# ProPrj_STM_L_2026-07-04.net
KiCad netlist of a schematic drawn in EasyEDA Pro
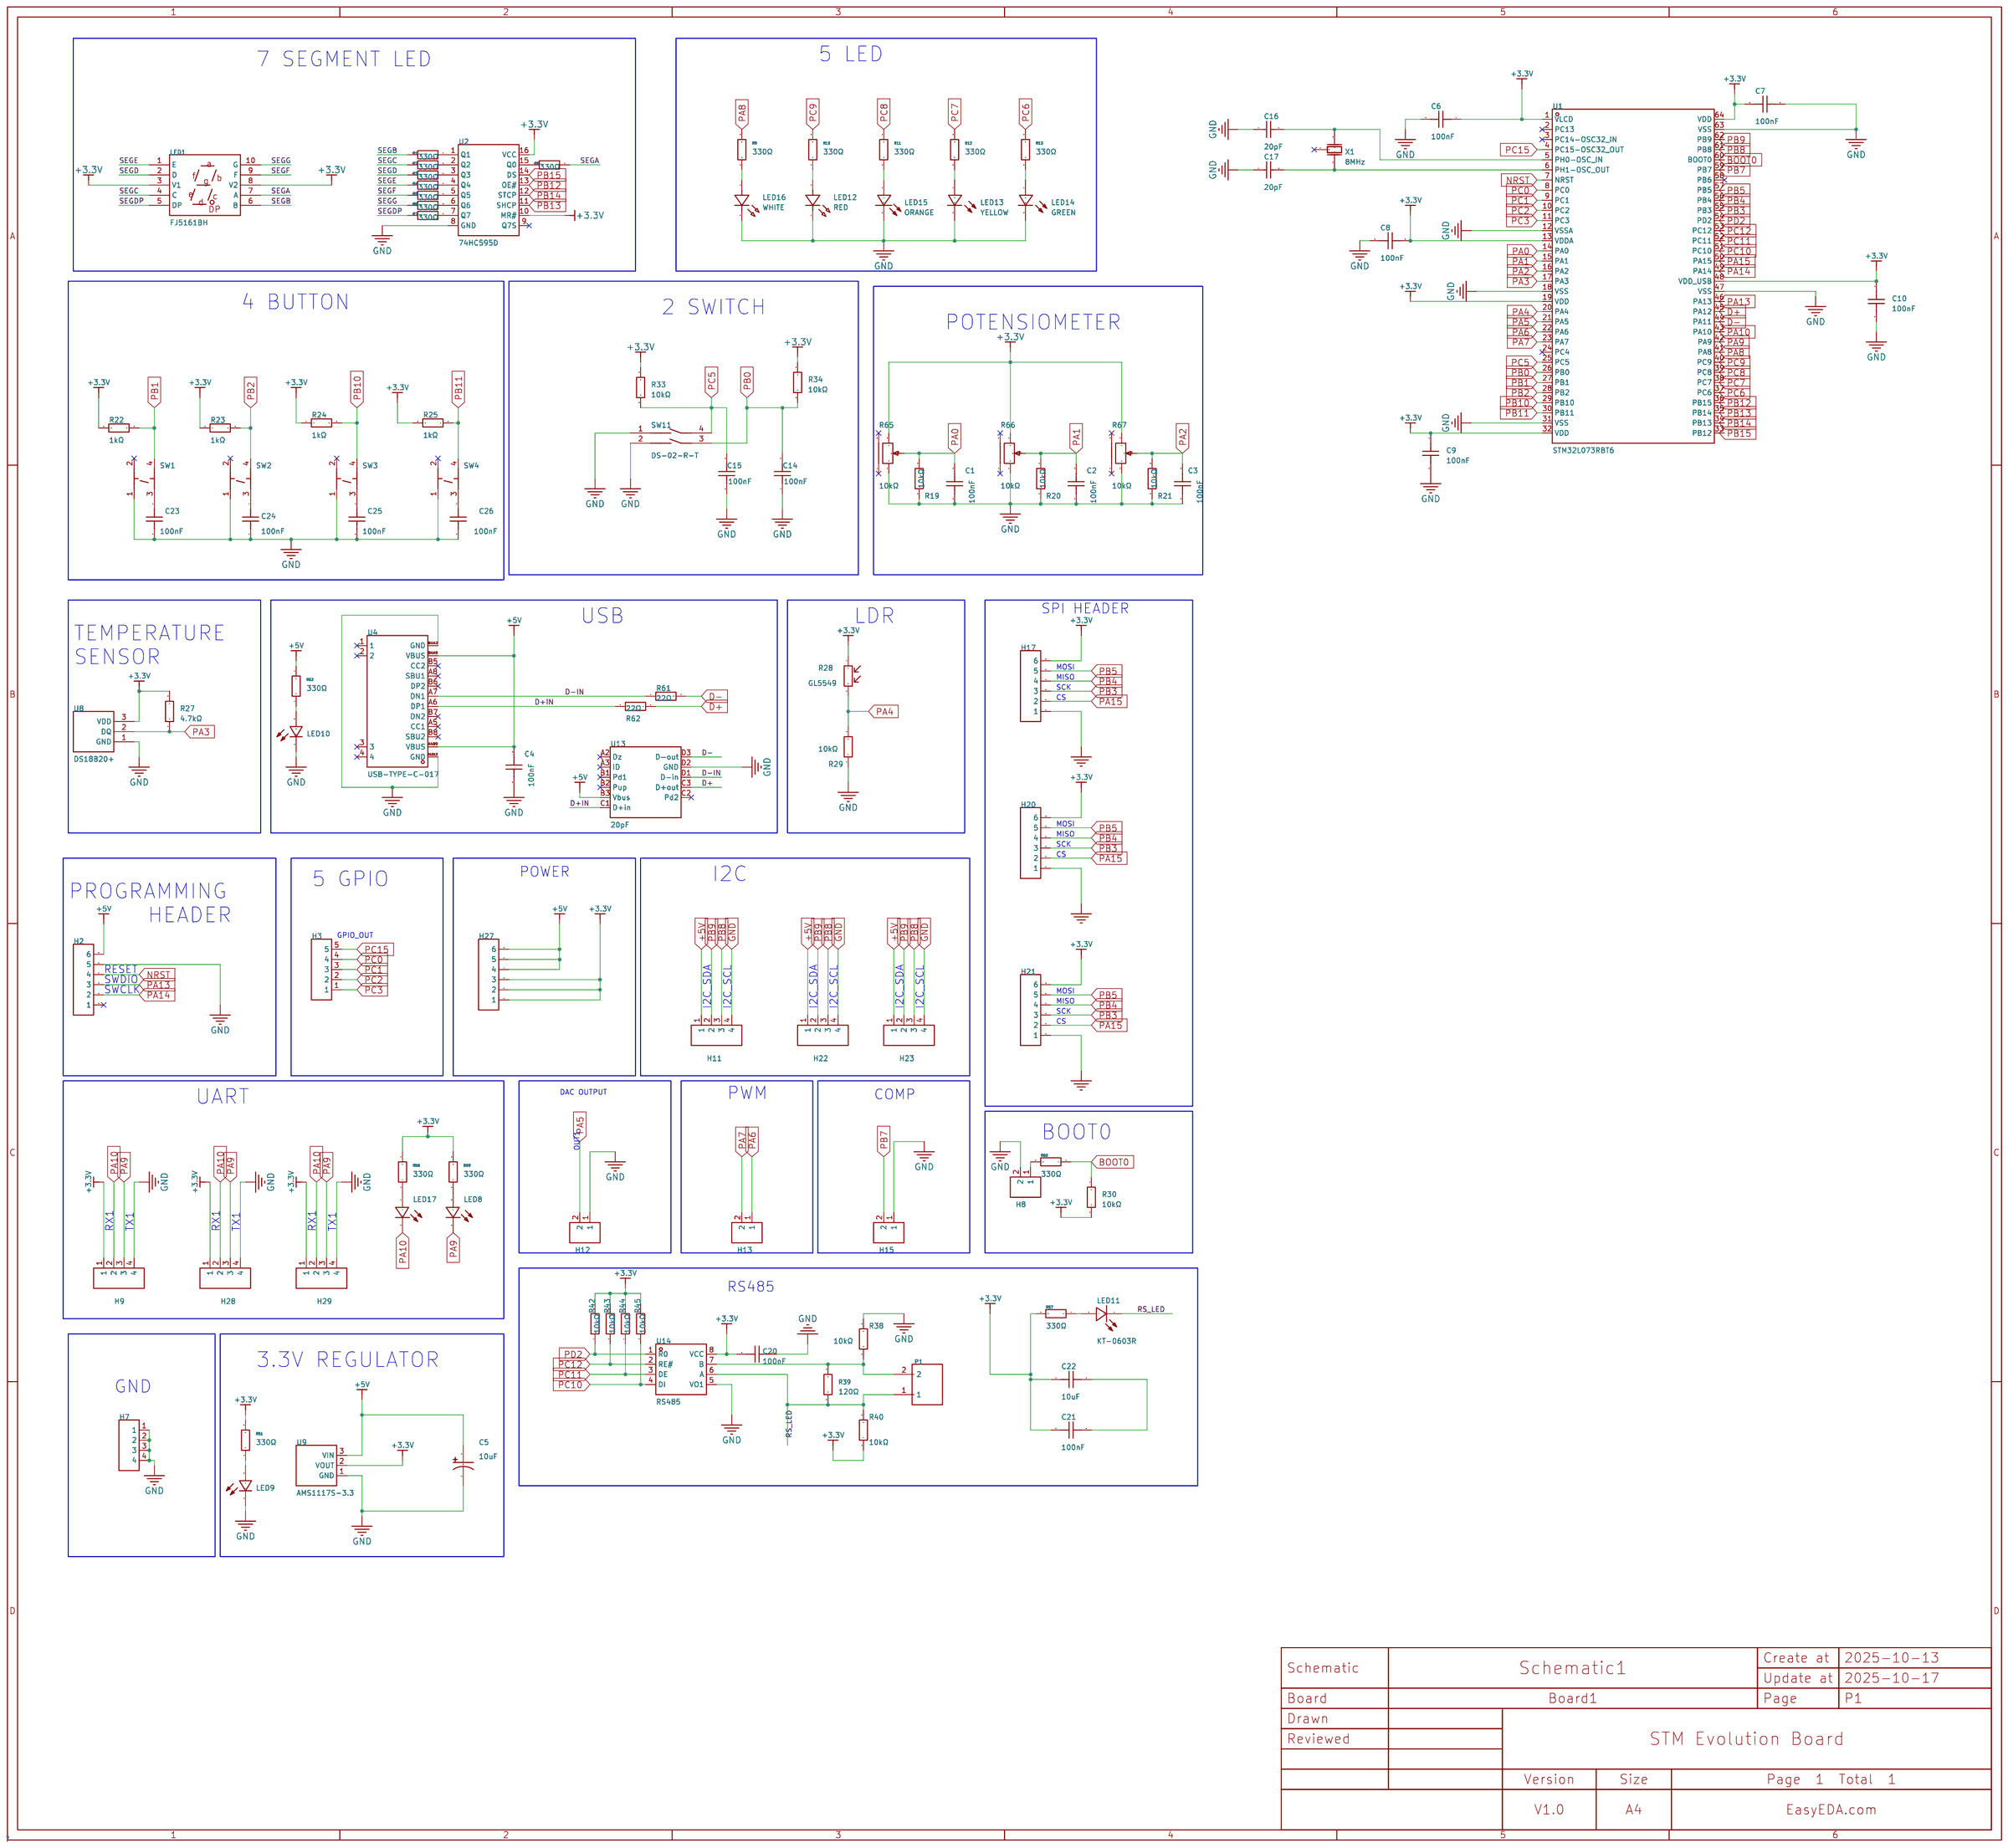
[diagram p0: schematic sheet]

(export (version "E")
  (design (tool "Eeschema 10.0.6"))
  (components
    (comp (ref "C1")
      (value "100nF")
      (footprint "easyedapro:C0603")
      (fields
        (field (name "Manufacturer Part") "CC0603KRX7R9BB104")
        (field (name "Manufacturer") "YAGEO(国巨)")
      )
      (libsource (lib "easyedapro") (part "CC0603KRX7R9BB104"))
    )
    (comp (ref "C2")
      (value "100nF")
      (footprint "easyedapro:C0603")
      (fields
        (field (name "Manufacturer Part") "CC0603KRX7R9BB104")
        (field (name "Manufacturer") "YAGEO(国巨)")
      )
      (libsource (lib "easyedapro") (part "CC0603KRX7R9BB104"))
    )
    (comp (ref "C3")
      (value "100nF")
      (footprint "easyedapro:C0603")
      (fields
        (field (name "Manufacturer Part") "CC0603KRX7R9BB104")
        (field (name "Manufacturer") "YAGEO(国巨)")
      )
      (libsource (lib "easyedapro") (part "CC0603KRX7R9BB104"))
    )
    (comp (ref "C4")
      (value "100nF")
      (footprint "easyedapro:C0603")
      (fields
        (field (name "Manufacturer Part") "CC0603KRX7R9BB104")
        (field (name "Manufacturer") "YAGEO(国巨)")
      )
      (libsource (lib "easyedapro") (part "CC0603KRX7R9BB104"))
    )
    (comp (ref "C5")
      (value "10uF")
      (footprint "easyedapro:CAP-SMD_L3.2-W1.6")
      (fields (field (name "Manufacturer Part") "NOJA106M010RWJ") (field (name "Manufacturer") "Kyocera AVX"))
      (libsource (lib "easyedapro") (part "NOJA106M010RWJ"))
    )
    (comp (ref "C6")
      (value "100nF")
      (footprint "easyedapro:C0603")
      (fields
        (field (name "Manufacturer Part") "CC0603KRX7R9BB104")
        (field (name "Manufacturer") "YAGEO(国巨)")
      )
      (libsource (lib "easyedapro") (part "CC0603KRX7R9BB104"))
    )
    (comp (ref "C7")
      (value "100nF")
      (footprint "easyedapro:C0603")
      (fields
        (field (name "Manufacturer Part") "CC0603KRX7R9BB104")
        (field (name "Manufacturer") "YAGEO(国巨)")
      )
      (libsource (lib "easyedapro") (part "CC0603KRX7R9BB104"))
    )
    (comp (ref "C8")
      (value "100nF")
      (footprint "easyedapro:C0603")
      (fields
        (field (name "Manufacturer Part") "CC0603KRX7R9BB104")
        (field (name "Manufacturer") "YAGEO(国巨)")
      )
      (libsource (lib "easyedapro") (part "CC0603KRX7R9BB104"))
    )
    (comp (ref "C9")
      (value "100nF")
      (footprint "easyedapro:C0603")
      (fields
        (field (name "Manufacturer Part") "CC0603KRX7R9BB104")
        (field (name "Manufacturer") "YAGEO(国巨)")
      )
      (libsource (lib "easyedapro") (part "CC0603KRX7R9BB104"))
    )
    (comp (ref "C10")
      (value "100nF")
      (footprint "easyedapro:C0603")
      (fields
        (field (name "Manufacturer Part") "CC0603KRX7R9BB104")
        (field (name "Manufacturer") "YAGEO(国巨)")
      )
      (libsource (lib "easyedapro") (part "CC0603KRX7R9BB104"))
    )
    (comp (ref "C14")
      (value "100nF")
      (footprint "easyedapro:C0603")
      (fields
        (field (name "Manufacturer Part") "CC0603KRX7R9BB104")
        (field (name "Manufacturer") "YAGEO(国巨)")
      )
      (libsource (lib "easyedapro") (part "CC0603KRX7R9BB104"))
    )
    (comp (ref "C15")
      (value "100nF")
      (footprint "easyedapro:C0603")
      (fields
        (field (name "Manufacturer Part") "CC0603KRX7R9BB104")
        (field (name "Manufacturer") "YAGEO(国巨)")
      )
      (libsource (lib "easyedapro") (part "CC0603KRX7R9BB104"))
    )
    (comp (ref "C16")
      (value "20pF")
      (footprint "easyedapro:C0603")
      (fields
        (field (name "Manufacturer Part") "CL10C200JB8NNNC")
        (field (name "Manufacturer") "SAMSUNG(三星)")
      )
      (libsource (lib "easyedapro") (part "CL10C200JB8NNNC"))
    )
    (comp (ref "C17")
      (value "20pF")
      (footprint "easyedapro:C0603")
      (fields
        (field (name "Manufacturer Part") "CL10C200JB8NNNC")
        (field (name "Manufacturer") "SAMSUNG(三星)")
      )
      (libsource (lib "easyedapro") (part "CL10C200JB8NNNC"))
    )
    (comp (ref "C20")
      (value "100nF")
      (footprint "easyedapro:C0603")
      (fields
        (field (name "Manufacturer Part") "CC0603KRX7R9BB104")
        (field (name "Manufacturer") "YAGEO(国巨)")
      )
      (libsource (lib "easyedapro") (part "CC0603KRX7R9BB104"))
    )
    (comp (ref "C21")
      (value "100nF")
      (footprint "easyedapro:C0603")
      (fields
        (field (name "Manufacturer Part") "CC0603KRX7R9BB104")
        (field (name "Manufacturer") "YAGEO(国巨)")
      )
      (libsource (lib "easyedapro") (part "CC0603KRX7R9BB104"))
    )
    (comp (ref "C22")
      (value "10uF")
      (footprint "easyedapro:C0603")
      (fields
        (field (name "Manufacturer Part") "CL10A106KP8NNNC")
        (field (name "Manufacturer") "SAMSUNG(三星)")
      )
      (libsource (lib "easyedapro") (part "CL10A106KP8NNNC"))
    )
    (comp (ref "C23")
      (value "100nF")
      (footprint "easyedapro:C0603")
      (description "Capacitance:100nF Tolerance:±10% Tolerance:±10% Voltage Rating:50V Temperature Coefficient:X7R")
      (fields
        (field (name "Manufacturer Part") "CC0603KRX7R9BB104")
        (field (name "Manufacturer") "YAGEO(国巨)")
      )
      (libsource (lib "easyedapro") (part "CC0603KRX7R9BB104"))
    )
    (comp (ref "C24")
      (value "100nF")
      (footprint "easyedapro:C0603")
      (description "Capacitance:100nF Tolerance:±10% Tolerance:±10% Voltage Rating:50V Temperature Coefficient:X7R")
      (fields
        (field (name "Manufacturer Part") "CC0603KRX7R9BB104")
        (field (name "Manufacturer") "YAGEO(国巨)")
      )
      (libsource (lib "easyedapro") (part "CC0603KRX7R9BB104"))
    )
    (comp (ref "C25")
      (value "100nF")
      (footprint "easyedapro:C0603")
      (description "Capacitance:100nF Tolerance:±10% Tolerance:±10% Voltage Rating:50V Temperature Coefficient:X7R")
      (fields
        (field (name "Manufacturer Part") "CC0603KRX7R9BB104")
        (field (name "Manufacturer") "YAGEO(国巨)")
      )
      (libsource (lib "easyedapro") (part "CC0603KRX7R9BB104"))
    )
    (comp (ref "C26")
      (value "100nF")
      (footprint "easyedapro:C0603")
      (description "Capacitance:100nF Tolerance:±10% Tolerance:±10% Voltage Rating:50V Temperature Coefficient:X7R")
      (fields
        (field (name "Manufacturer Part") "CC0603KRX7R9BB104")
        (field (name "Manufacturer") "YAGEO(国巨)")
      )
      (libsource (lib "easyedapro") (part "CC0603KRX7R9BB104"))
    )
    (comp (ref "H2")
      (value "2.54-1x6P直针")
      (footprint "easyedapro:HDR-TH_6P-P2.54-V-M-1")
      (fields (field (name "Manufacturer") "BOOMELE(博穆精密)"))
      (libsource (lib "easyedapro") (part "Header-Male-2.54_1x6"))
    )
    (comp (ref "H3")
      (value "PH2.54-1X5P-H25")
      (footprint "easyedapro:HDR-TH_5P-P2.54-V-M-3")
      (fields (field (name "Manufacturer") "JXTCONN(聚兴泰)"))
      (libsource (lib "easyedapro") (part "PH2.54-1X5P-H25"))
    )
    (comp (ref "H7")
      (value "PZ2.54-1X4P-H25")
      (footprint "easyedapro:HDR-TH_4P-P2.54-V-M")
      (fields (field (name "Manufacturer") "JXTCONN(聚兴泰)"))
      (libsource (lib "easyedapro") (part "PZ2.54-1X4P-H25"))
    )
    (comp (ref "H8")
      (value "1.27-1*2P针")
      (footprint "easyedapro:HDR-TH_2P-P1.27-V-M")
      (fields (field (name "Manufacturer") "BOOMELE(博穆精密)"))
      (libsource (lib "easyedapro") (part "1.27MM/1*2P"))
    )
    (comp (ref "H9")
      (value "PZ2.54-1X4P-H25")
      (footprint "easyedapro:HDR-TH_4P-P2.54-V-M")
      (fields (field (name "Manufacturer") "JXTCONN(聚兴泰)"))
      (libsource (lib "easyedapro") (part "PZ2.54-1X4P-H25"))
    )
    (comp (ref "H11")
      (value "PZ2.54-1X4P-H25")
      (footprint "easyedapro:HDR-TH_4P-P2.54-V-M")
      (fields (field (name "Manufacturer") "JXTCONN(聚兴泰)"))
      (libsource (lib "easyedapro") (part "PZ2.54-1X4P-H25"))
    )
    (comp (ref "H12")
      (value "1.27-1*2P针")
      (footprint "easyedapro:HDR-TH_2P-P1.27-V-M")
      (fields (field (name "Manufacturer") "BOOMELE(博穆精密)"))
      (libsource (lib "easyedapro") (part "1.27MM/1*2P"))
    )
    (comp (ref "H13")
      (value "1.27-1*2P针")
      (footprint "easyedapro:HDR-TH_2P-P1.27-V-M")
      (fields (field (name "Manufacturer") "BOOMELE(博穆精密)"))
      (libsource (lib "easyedapro") (part "1.27MM/1*2P"))
    )
    (comp (ref "H15")
      (value "1.27-1*2P针")
      (footprint "easyedapro:HDR-TH_2P-P1.27-V-M")
      (fields (field (name "Manufacturer") "BOOMELE(博穆精密)"))
      (libsource (lib "easyedapro") (part "1.27MM/1*2P"))
    )
    (comp (ref "H17")
      (value "2.54-1x6P直针")
      (footprint "easyedapro:HDR-TH_6P-P2.54-V-M-1")
      (fields (field (name "Manufacturer") "BOOMELE(博穆精密)"))
      (libsource (lib "easyedapro") (part "Header-Male-2.54_1x6"))
    )
    (comp (ref "H20")
      (value "2.54-1x6P直针")
      (footprint "easyedapro:HDR-TH_6P-P2.54-V-M-1")
      (fields (field (name "Manufacturer") "BOOMELE(博穆精密)"))
      (libsource (lib "easyedapro") (part "Header-Male-2.54_1x6"))
    )
    (comp (ref "H21")
      (value "2.54-1x6P直针")
      (footprint "easyedapro:HDR-TH_6P-P2.54-V-M-1")
      (fields (field (name "Manufacturer") "BOOMELE(博穆精密)"))
      (libsource (lib "easyedapro") (part "Header-Male-2.54_1x6"))
    )
    (comp (ref "H22")
      (value "PZ2.54-1X4P-H25")
      (footprint "easyedapro:HDR-TH_4P-P2.54-V-M")
      (fields (field (name "Manufacturer") "JXTCONN(聚兴泰)"))
      (libsource (lib "easyedapro") (part "PZ2.54-1X4P-H25"))
    )
    (comp (ref "H23")
      (value "PZ2.54-1X4P-H25")
      (footprint "easyedapro:HDR-TH_4P-P2.54-V-M")
      (fields (field (name "Manufacturer") "JXTCONN(聚兴泰)"))
      (libsource (lib "easyedapro") (part "PZ2.54-1X4P-H25"))
    )
    (comp (ref "H27")
      (value "2.54-1x6P直针")
      (footprint "easyedapro:HDR-TH_6P-P2.54-V-M-1")
      (fields (field (name "Manufacturer") "BOOMELE(博穆精密)"))
      (libsource (lib "easyedapro") (part "Header-Male-2.54_1x6"))
    )
    (comp (ref "H28")
      (value "PZ2.54-1X4P-H25")
      (footprint "easyedapro:HDR-TH_4P-P2.54-V-M")
      (fields (field (name "Manufacturer") "JXTCONN(聚兴泰)"))
      (libsource (lib "easyedapro") (part "PZ2.54-1X4P-H25"))
    )
    (comp (ref "H29")
      (value "PZ2.54-1X4P-H25")
      (footprint "easyedapro:HDR-TH_4P-P2.54-V-M")
      (fields (field (name "Manufacturer") "JXTCONN(聚兴泰)"))
      (libsource (lib "easyedapro") (part "PZ2.54-1X4P-H25"))
    )
    (comp (ref "LED1")
      (value "FJ5161BH")
      (footprint "easyedapro:LED-SEG-TH_FJ5161BH")
      (fields (field (name "Manufacturer") "志浩"))
      (libsource (lib "easyedapro") (part "FJ5161BH"))
    )
    (comp (ref "LED8")
      (value "YLED0603R")
      (footprint "easyedapro:LED0603-FD")
      (fields (field (name "Manufacturer") "YONGYUTAI(永裕泰)"))
      (libsource (lib "easyedapro") (part "YLED0603R"))
    )
    (comp (ref "LED9")
      (value "NCD0603G1")
      (footprint "easyedapro:LED0603-RD_1")
      (fields (field (name "Manufacturer") "国星光电"))
      (libsource (lib "easyedapro") (part "FC-D1608UGK-520D10"))
    )
    (comp (ref "LED10")
      (value "NCD0603G1")
      (footprint "easyedapro:LED0603-RD_1")
      (fields (field (name "Manufacturer") "国星光电"))
      (libsource (lib "easyedapro") (part "FC-D1608UGK-520D10"))
    )
    (comp (ref "LED11")
      (value "KT-0603R")
      (footprint "easyedapro:LED0603-RD")
      (fields (field (name "Manufacturer") "KENTO"))
      (libsource (lib "easyedapro") (part "KT-0603R"))
    )
    (comp (ref "LED12")
      (value "RED")
      (footprint "easyedapro:LED-TH_BD3.8-P2.54-RD")
      (fields (field (name "Manufacturer") "XINGLIGHT(成兴光)"))
      (libsource (lib "easyedapro") (part "XL-302SURD"))
    )
    (comp (ref "LED13")
      (value "YELLOW")
      (footprint "easyedapro:LED-TH_BD4.0-P2.54-FD")
      (fields (field (name "Manufacturer") "EVERLIGHT(亿光)"))
      (libsource (lib "easyedapro") (part "204-10UYT/S530-A3"))
    )
    (comp (ref "LED14")
      (value "GREEN")
      (footprint "easyedapro:LED-TH_BD4.0-P2.54-FD")
      (fields (field (name "Manufacturer") "EVERLIGHT(亿光)"))
      (libsource (lib "easyedapro") (part "204-10UYT/S530-A3"))
    )
    (comp (ref "LED15")
      (value "ORANGE")
      (footprint "easyedapro:LED-TH_BD3.0-P2.54-FD")
      (fields (field (name "Manufacturer") "TOGIALED(统佳)"))
      (libsource (lib "easyedapro") (part "TJ-L3FYTXHAMCGLFLC0A-A5"))
    )
    (comp (ref "LED16")
      (value "WHITE")
      (footprint "easyedapro:LED-TH_BD3.8-P2.54-FD_WHITE")
      (fields (field (name "Manufacturer") "XINGLIGHT(成兴光)"))
      (libsource (lib "easyedapro") (part "XL-302UWC"))
    )
    (comp (ref "LED17")
      (value "YLED0603R")
      (footprint "easyedapro:LED0603-FD")
      (fields (field (name "Manufacturer") "YONGYUTAI(永裕泰)"))
      (libsource (lib "easyedapro") (part "YLED0603R"))
    )
    (comp (ref "P1")
      (value "WJ126V-5.0-2P")
      (footprint "easyedapro:CONN-TH_WJ126V-5.0-2P")
      (fields (field (name "Manufacturer") "KANGNEX(康奈克斯电气)"))
      (libsource (lib "easyedapro") (part "WJ126V-5.0-2P"))
    )
    (comp (ref "R1")
      (value "330Ω")
      (footprint "easyedapro:R0603")
      (fields (field (name "Manufacturer Part") "RC0603FR-07330RL") (field (name "Manufacturer") "YAGEO(国巨)"))
      (libsource (lib "easyedapro") (part "RC0603FR-07330RL"))
    )
    (comp (ref "R2")
      (value "330Ω")
      (footprint "easyedapro:R0603")
      (fields (field (name "Manufacturer Part") "RC0603FR-07330RL") (field (name "Manufacturer") "YAGEO(国巨)"))
      (libsource (lib "easyedapro") (part "RC0603FR-07330RL"))
    )
    (comp (ref "R3")
      (value "330Ω")
      (footprint "easyedapro:R0603")
      (fields (field (name "Manufacturer Part") "RC0603FR-07330RL") (field (name "Manufacturer") "YAGEO(国巨)"))
      (libsource (lib "easyedapro") (part "RC0603FR-07330RL"))
    )
    (comp (ref "R4")
      (value "330Ω")
      (footprint "easyedapro:R0603")
      (fields (field (name "Manufacturer Part") "RC0603FR-07330RL") (field (name "Manufacturer") "YAGEO(国巨)"))
      (libsource (lib "easyedapro") (part "RC0603FR-07330RL"))
    )
    (comp (ref "R5")
      (value "330Ω")
      (footprint "easyedapro:R0603")
      (fields (field (name "Manufacturer Part") "RC0603FR-07330RL") (field (name "Manufacturer") "YAGEO(国巨)"))
      (libsource (lib "easyedapro") (part "RC0603FR-07330RL"))
    )
    (comp (ref "R6")
      (value "330Ω")
      (footprint "easyedapro:R0603")
      (fields (field (name "Manufacturer Part") "RC0603FR-07330RL") (field (name "Manufacturer") "YAGEO(国巨)"))
      (libsource (lib "easyedapro") (part "RC0603FR-07330RL"))
    )
    (comp (ref "R7")
      (value "330Ω")
      (footprint "easyedapro:R0603")
      (fields (field (name "Manufacturer Part") "RC0603FR-07330RL") (field (name "Manufacturer") "YAGEO(国巨)"))
      (libsource (lib "easyedapro") (part "RC0603FR-07330RL"))
    )
    (comp (ref "R8")
      (value "330Ω")
      (footprint "easyedapro:R0603")
      (fields (field (name "Manufacturer Part") "RC0603FR-07330RL") (field (name "Manufacturer") "YAGEO(国巨)"))
      (libsource (lib "easyedapro") (part "RC0603FR-07330RL"))
    )
    (comp (ref "R9")
      (value "330Ω")
      (footprint "easyedapro:R0603")
      (fields (field (name "Manufacturer Part") "RC0603FR-07330RL") (field (name "Manufacturer") "YAGEO(国巨)"))
      (libsource (lib "easyedapro") (part "RC0603FR-07330RL"))
    )
    (comp (ref "R10")
      (value "330Ω")
      (footprint "easyedapro:R0603")
      (fields (field (name "Manufacturer Part") "RC0603FR-07330RL") (field (name "Manufacturer") "YAGEO(国巨)"))
      (libsource (lib "easyedapro") (part "RC0603FR-07330RL"))
    )
    (comp (ref "R11")
      (value "330Ω")
      (footprint "easyedapro:R0603")
      (fields (field (name "Manufacturer Part") "RC0603FR-07330RL") (field (name "Manufacturer") "YAGEO(国巨)"))
      (libsource (lib "easyedapro") (part "RC0603FR-07330RL"))
    )
    (comp (ref "R12")
      (value "330Ω")
      (footprint "easyedapro:R0603")
      (fields (field (name "Manufacturer Part") "RC0603FR-07330RL") (field (name "Manufacturer") "YAGEO(国巨)"))
      (libsource (lib "easyedapro") (part "RC0603FR-07330RL"))
    )
    (comp (ref "R13")
      (value "330Ω")
      (footprint "easyedapro:R0603")
      (fields (field (name "Manufacturer Part") "RC0603FR-07330RL") (field (name "Manufacturer") "YAGEO(国巨)"))
      (libsource (lib "easyedapro") (part "RC0603FR-07330RL"))
    )
    (comp (ref "R19")
      (value "10kΩ")
      (footprint "easyedapro:R0603")
      (fields (field (name "Manufacturer Part") "RC0603FR-0710KL") (field (name "Manufacturer") "YAGEO(国巨)"))
      (libsource (lib "easyedapro") (part "RC0603FR-0710KL"))
    )
    (comp (ref "R20")
      (value "10kΩ")
      (footprint "easyedapro:R0603")
      (fields (field (name "Manufacturer Part") "RC0603FR-0710KL") (field (name "Manufacturer") "YAGEO(国巨)"))
      (libsource (lib "easyedapro") (part "RC0603FR-0710KL"))
    )
    (comp (ref "R21")
      (value "10kΩ")
      (footprint "easyedapro:R0603")
      (fields (field (name "Manufacturer Part") "RC0603FR-0710KL") (field (name "Manufacturer") "YAGEO(国巨)"))
      (libsource (lib "easyedapro") (part "RC0603FR-0710KL"))
    )
    (comp (ref "R22")
      (value "1kΩ")
      (footprint "easyedapro:R0603")
      (fields
        (field (name "Manufacturer Part") "RC0603FR-071KL")
        (field (name "Manufacturer") "YAGEO(国巨)")
        (field (name "Tolerance") "±1%")
      )
      (libsource (lib "easyedapro") (part "RC0603FR-071KL"))
    )
    (comp (ref "R23")
      (value "1kΩ")
      (footprint "easyedapro:R0603")
      (fields
        (field (name "Manufacturer Part") "RC0603FR-071KL")
        (field (name "Manufacturer") "YAGEO(国巨)")
        (field (name "Tolerance") "±1%")
      )
      (libsource (lib "easyedapro") (part "RC0603FR-071KL"))
    )
    (comp (ref "R24")
      (value "1kΩ")
      (footprint "easyedapro:R0603")
      (fields
        (field (name "Manufacturer Part") "RC0603FR-071KL")
        (field (name "Manufacturer") "YAGEO(国巨)")
        (field (name "Tolerance") "±1%")
      )
      (libsource (lib "easyedapro") (part "RC0603FR-071KL"))
    )
    (comp (ref "R25")
      (value "1kΩ")
      (footprint "easyedapro:R0603")
      (fields
        (field (name "Manufacturer Part") "RC0603FR-071KL")
        (field (name "Manufacturer") "YAGEO(国巨)")
        (field (name "Tolerance") "±1%")
      )
      (libsource (lib "easyedapro") (part "RC0603FR-071KL"))
    )
    (comp (ref "R27")
      (value "4.7kΩ")
      (footprint "easyedapro:R0603")
      (fields (field (name "Manufacturer Part") "RC0603FR-074K7L") (field (name "Manufacturer") "YAGEO(国巨)"))
      (libsource (lib "easyedapro") (part "RC0603FR-074K7L"))
    )
    (comp (ref "R28")
      (value "GL5549")
      (footprint "easyedapro:RES-TH_L5.1-W4.3-P3.40-D0.5")
      (fields (field (name "Manufacturer") "森霸"))
      (libsource (lib "easyedapro") (part "GL5549"))
    )
    (comp (ref "R29")
      (value "10kΩ")
      (footprint "easyedapro:R0603")
      (fields (field (name "Manufacturer Part") "RC0603FR-0710KL") (field (name "Manufacturer") "YAGEO(国巨)"))
      (libsource (lib "easyedapro") (part "RC0603FR-0710KL"))
    )
    (comp (ref "R30")
      (value "10kΩ")
      (footprint "easyedapro:R0603")
      (fields (field (name "Manufacturer Part") "RC0603FR-0710KL") (field (name "Manufacturer") "YAGEO(国巨)"))
      (libsource (lib "easyedapro") (part "RC0603FR-0710KL"))
    )
    (comp (ref "R33")
      (value "10kΩ")
      (footprint "easyedapro:R0603")
      (fields (field (name "Manufacturer Part") "RC0603FR-0710KL") (field (name "Manufacturer") "YAGEO(国巨)"))
      (libsource (lib "easyedapro") (part "RC0603FR-0710KL"))
    )
    (comp (ref "R34")
      (value "10kΩ")
      (footprint "easyedapro:R0603")
      (fields (field (name "Manufacturer Part") "RC0603FR-0710KL") (field (name "Manufacturer") "YAGEO(国巨)"))
      (libsource (lib "easyedapro") (part "RC0603FR-0710KL"))
    )
    (comp (ref "R38")
      (value "10kΩ")
      (footprint "easyedapro:R0603")
      (fields (field (name "Manufacturer Part") "RC0603FR-0710KL") (field (name "Manufacturer") "YAGEO(国巨)"))
      (libsource (lib "easyedapro") (part "RC0603FR-0710KL"))
    )
    (comp (ref "R39")
      (value "120Ω")
      (footprint "easyedapro:R0603")
      (fields
        (field (name "Manufacturer Part") "0603WAF1200T5E")
        (field (name "Manufacturer") "UNI-ROYAL(厚声)")
      )
      (libsource (lib "easyedapro") (part "0603WAF1200T5E"))
    )
    (comp (ref "R40")
      (value "10kΩ")
      (footprint "easyedapro:R0603")
      (fields (field (name "Manufacturer Part") "RC0603FR-0710KL") (field (name "Manufacturer") "YAGEO(国巨)"))
      (libsource (lib "easyedapro") (part "RC0603FR-0710KL"))
    )
    (comp (ref "R42")
      (value "10kΩ")
      (footprint "easyedapro:R0603")
      (fields (field (name "Manufacturer Part") "RC0603FR-0710KL") (field (name "Manufacturer") "YAGEO(国巨)"))
      (libsource (lib "easyedapro") (part "RC0603FR-0710KL"))
    )
    (comp (ref "R43")
      (value "10kΩ")
      (footprint "easyedapro:R0603")
      (fields (field (name "Manufacturer Part") "RC0603FR-0710KL") (field (name "Manufacturer") "YAGEO(国巨)"))
      (libsource (lib "easyedapro") (part "RC0603FR-0710KL"))
    )
    (comp (ref "R44")
      (value "10kΩ")
      (footprint "easyedapro:R0603")
      (fields (field (name "Manufacturer Part") "RC0603FR-0710KL") (field (name "Manufacturer") "YAGEO(国巨)"))
      (libsource (lib "easyedapro") (part "RC0603FR-0710KL"))
    )
    (comp (ref "R45")
      (value "10kΩ")
      (footprint "easyedapro:R0603")
      (fields (field (name "Manufacturer Part") "RC0603FR-0710KL") (field (name "Manufacturer") "YAGEO(国巨)"))
      (libsource (lib "easyedapro") (part "RC0603FR-0710KL"))
    )
    (comp (ref "R51")
      (value "330Ω")
      (footprint "easyedapro:R0603")
      (fields (field (name "Manufacturer Part") "RC0603FR-07330RL") (field (name "Manufacturer") "YAGEO(国巨)"))
      (libsource (lib "easyedapro") (part "RC0603FR-07330RL"))
    )
    (comp (ref "R52")
      (value "330Ω")
      (footprint "easyedapro:R0603")
      (fields (field (name "Manufacturer Part") "RC0603FR-07330RL") (field (name "Manufacturer") "YAGEO(国巨)"))
      (libsource (lib "easyedapro") (part "RC0603FR-07330RL"))
    )
    (comp (ref "R57")
      (value "330Ω")
      (footprint "easyedapro:R0603")
      (fields (field (name "Manufacturer Part") "RC0603FR-07330RL") (field (name "Manufacturer") "YAGEO(国巨)"))
      (libsource (lib "easyedapro") (part "RC0603FR-07330RL"))
    )
    (comp (ref "R58")
      (value "330Ω")
      (footprint "easyedapro:R0603")
      (fields (field (name "Manufacturer Part") "RC0603FR-07330RL") (field (name "Manufacturer") "YAGEO(国巨)"))
      (libsource (lib "easyedapro") (part "RC0603FR-07330RL"))
    )
    (comp (ref "R59")
      (value "330Ω")
      (footprint "easyedapro:R0603")
      (fields (field (name "Manufacturer Part") "RC0603FR-07330RL") (field (name "Manufacturer") "YAGEO(国巨)"))
      (libsource (lib "easyedapro") (part "RC0603FR-07330RL"))
    )
    (comp (ref "R60")
      (value "330Ω")
      (footprint "easyedapro:R0603")
      (fields (field (name "Manufacturer Part") "RC0603FR-07330RL") (field (name "Manufacturer") "YAGEO(国巨)"))
      (libsource (lib "easyedapro") (part "RC0603FR-07330RL"))
    )
    (comp (ref "R61")
      (value "22Ω")
      (footprint "easyedapro:R0603")
      (fields
        (field (name "Manufacturer Part") "0603WAF220JT5E")
        (field (name "Manufacturer") "UNI-ROYAL(厚声)")
      )
      (libsource (lib "easyedapro") (part "0603WAF220JT5E"))
    )
    (comp (ref "R62")
      (value "22Ω")
      (footprint "easyedapro:R0603")
      (fields
        (field (name "Manufacturer Part") "0603WAF220JT5E")
        (field (name "Manufacturer") "UNI-ROYAL(厚声)")
      )
      (libsource (lib "easyedapro") (part "0603WAF220JT5E"))
    )
    (comp (ref "R65")
      (value "10kΩ")
      (footprint "easyedapro:RES-ADJ-TH_RK09K1130AJ3")
      (fields
        (field (name "Manufacturer Part") "RK09K1130AP5")
        (field (name "Manufacturer") "ALPSALPINE(阿尔卑斯阿尔派)")
      )
      (libsource (lib "easyedapro") (part "RK09K1130AP5"))
    )
    (comp (ref "R66")
      (value "10kΩ")
      (footprint "easyedapro:RES-ADJ-TH_RK09K1130AJ3")
      (fields
        (field (name "Manufacturer Part") "RK09K1130AP5")
        (field (name "Manufacturer") "ALPSALPINE(阿尔卑斯阿尔派)")
      )
      (libsource (lib "easyedapro") (part "RK09K1130AP5"))
    )
    (comp (ref "R67")
      (value "10kΩ")
      (footprint "easyedapro:RES-ADJ-TH_RK09K1130AJ3")
      (fields
        (field (name "Manufacturer Part") "RK09K1130AP5")
        (field (name "Manufacturer") "ALPSALPINE(阿尔卑斯阿尔派)")
      )
      (libsource (lib "easyedapro") (part "RK09K1130AP5"))
    )
    (comp (ref "SW1")
      (value "LXW-TS-6X6X5-SMD")
      (footprint "easyedapro:SW-SMD_4P-L6.0-W6.0-P4.50-LS7.2")
      (fields (field (name "Manufacturer") "LXWCONN(连兴旺电子)"))
      (libsource (lib "easyedapro") (part "LXW-TS-6X6X5-SMD"))
    )
    (comp (ref "SW2")
      (value "LXW-TS-6X6X5-SMD")
      (footprint "easyedapro:SW-SMD_4P-L6.0-W6.0-P4.50-LS7.2")
      (fields (field (name "Manufacturer") "LXWCONN(连兴旺电子)"))
      (libsource (lib "easyedapro") (part "LXW-TS-6X6X5-SMD"))
    )
    (comp (ref "SW3")
      (value "LXW-TS-6X6X5-SMD")
      (footprint "easyedapro:SW-SMD_4P-L6.0-W6.0-P4.50-LS7.2")
      (fields (field (name "Manufacturer") "LXWCONN(连兴旺电子)"))
      (libsource (lib "easyedapro") (part "LXW-TS-6X6X5-SMD"))
    )
    (comp (ref "SW4")
      (value "LXW-TS-6X6X5-SMD")
      (footprint "easyedapro:SW-SMD_4P-L6.0-W6.0-P4.50-LS7.2")
      (fields (field (name "Manufacturer") "LXWCONN(连兴旺电子)"))
      (libsource (lib "easyedapro") (part "LXW-TS-6X6X5-SMD"))
    )
    (comp (ref "SW11")
      (value "DS-02-R-T")
      (footprint "easyedapro:SW-TH_4P-P2.54_DS-02R")
      (fields (field (name "Manufacturer") "康深"))
      (libsource (lib "easyedapro") (part "DS-02-R-T"))
    )
    (comp (ref "U1")
      (value "STM32L073RBT6")
      (footprint "easyedapro:LQFP-64_L10.0-W10.0-P0.50-LS12.0-BL")
      (fields (field (name "Manufacturer") "ST(意法半导体)"))
      (libsource (lib "easyedapro") (part "STM32L073RBT6_C2917159"))
    )
    (comp (ref "U2")
      (value "74HC595D")
      (footprint "easyedapro:SOIC-16_L9.9-W3.9-P1.27-LS6.0-BL")
      (fields (field (name "Manufacturer") "Nexperia(安世)"))
      (libsource (lib "easyedapro") (part "74HC595D,118"))
    )
    (comp (ref "U4")
      (value "USB-TYPE-C-017")
      (footprint "easyedapro:USB-TYPE-C-SMD_C9900008089")
      (fields (field (name "Manufacturer") "DEALON(德艺隆)"))
      (libsource (lib "easyedapro") (part "USB-TYPE-C-017"))
    )
    (comp (ref "U8")
      (value "DS18B20+")
      (footprint "easyedapro:TO-92-3_L4.9-W3.7-P1.27-L")
      (fields (field (name "Manufacturer") "ADI(亚德诺)/MAXIM(美信)"))
      (libsource (lib "easyedapro") (part "DS18B20+"))
    )
    (comp (ref "U9")
      (value "AMS1117S-3.3")
      (footprint "easyedapro:SOT-89-3_L4.5-W2.5-P1.50-LS4.1-BR")
      (fields (field (name "Manufacturer") "JSMSEMI(杰盛微)"))
      (libsource (lib "easyedapro") (part "AMS1117S-3.3"))
    )
    (comp (ref "U13")
      (value "20pF")
      (footprint "easyedapro:BGA-11_L2.0-W1.4-P0.50-TL")
      (fields (field (name "Manufacturer Part") "EMIF02-USB03F2") (field (name "Manufacturer") "ST(意法半导体)"))
      (libsource (lib "easyedapro") (part "EMIF02-USB03F2"))
    )
    (comp (ref "U14")
      (value "RS485")
      (footprint "easyedapro:SOP-8_L4.9-W3.9-P1.27-LS6.0-BL")
      (fields (field (name "Manufacturer") "GR(国睿)"))
      (libsource (lib "easyedapro") (part "RS485"))
    )
    (comp (ref "X1")
      (value "8MHz")
      (footprint "easyedapro:OSC-SMD_3P-L3.2-W1.3-P1.20-L")
      (fields
        (field (name "Manufacturer Part") "CSTNE8M00GH5C000R0")
        (field (name "Manufacturer") "muRata(村田)")
      )
      (libsource (lib "easyedapro") (part "CSTNE8M00GH5C000R0"))
    )
  )
  (nets
    (net (code "1") (name "+3.3V") (class "Default")
      (node (ref "C10") (pin "1") (pinfunction "1_1") (pintype "unspecified"))
      (node (ref "C20") (pin "2") (pinfunction "2_2") (pintype "unspecified"))
      (node (ref "C21") (pin "1") (pinfunction "1_1") (pintype "unspecified"))
      (node (ref "C22") (pin "1") (pinfunction "1_1") (pintype "unspecified"))
      (node (ref "C6") (pin "1") (pinfunction "1_1") (pintype "unspecified"))
      (node (ref "C7") (pin "2") (pinfunction "2_2") (pintype "unspecified"))
      (node (ref "C8") (pin "1") (pinfunction "1_1") (pintype "unspecified"))
      (node (ref "C9") (pin "1") (pinfunction "1_1") (pintype "unspecified"))
      (node (ref "H17") (pin "6") (pinfunction "6_6") (pintype "input"))
      (node (ref "H20") (pin "6") (pinfunction "6_6") (pintype "input"))
      (node (ref "H21") (pin "6") (pinfunction "6_6") (pintype "input"))
      (node (ref "H27") (pin "1") (pinfunction "1_1") (pintype "input"))
      (node (ref "H27") (pin "2") (pinfunction "2_2") (pintype "input"))
      (node (ref "H27") (pin "3") (pinfunction "3_3") (pintype "input"))
      (node (ref "H28") (pin "1") (pinfunction "1_1") (pintype "unspecified"))
      (node (ref "H29") (pin "1") (pinfunction "1_1") (pintype "unspecified"))
      (node (ref "H9") (pin "1") (pinfunction "1_1") (pintype "unspecified"))
      (node (ref "LED1") (pin "3") (pinfunction "V1_3") (pintype "input"))
      (node (ref "LED1") (pin "8") (pinfunction "V2_8") (pintype "input"))
      (node (ref "R22") (pin "2") (pinfunction "2_2") (pintype "input"))
      (node (ref "R23") (pin "1") (pinfunction "1_1") (pintype "input"))
      (node (ref "R24") (pin "1") (pinfunction "1_1") (pintype "input"))
      (node (ref "R25") (pin "2") (pinfunction "2_2") (pintype "input"))
      (node (ref "R27") (pin "2") (pinfunction "2_2") (pintype "input"))
      (node (ref "R28") (pin "1") (pinfunction "1_1") (pintype "input"))
      (node (ref "R30") (pin "2") (pinfunction "2_2") (pintype "input"))
      (node (ref "R33") (pin "1") (pinfunction "1_1") (pintype "input"))
      (node (ref "R34") (pin "1") (pinfunction "1_1") (pintype "input"))
      (node (ref "R40") (pin "1") (pinfunction "1_1") (pintype "input"))
      (node (ref "R42") (pin "2") (pinfunction "2_2") (pintype "input"))
      (node (ref "R43") (pin "2") (pinfunction "2_2") (pintype "input"))
      (node (ref "R44") (pin "2") (pinfunction "2_2") (pintype "input"))
      (node (ref "R45") (pin "2") (pinfunction "2_2") (pintype "input"))
      (node (ref "R51") (pin "2") (pinfunction "2_2") (pintype "input"))
      (node (ref "R57") (pin "2") (pinfunction "2_2") (pintype "input"))
      (node (ref "R58") (pin "2") (pinfunction "2_2") (pintype "input"))
      (node (ref "R59") (pin "2") (pinfunction "2_2") (pintype "input"))
      (node (ref "R65") (pin "3") (pinfunction "3_3") (pintype "input"))
      (node (ref "R66") (pin "3") (pinfunction "3_3") (pintype "input"))
      (node (ref "R67") (pin "3") (pinfunction "3_3") (pintype "input"))
      (node (ref "U1") (pin "1") (pinfunction "VLCD_1") (pintype "unspecified"))
      (node (ref "U1") (pin "13") (pinfunction "VDDA_13") (pintype "unspecified"))
      (node (ref "U1") (pin "19") (pinfunction "VDD_19") (pintype "unspecified"))
      (node (ref "U1") (pin "32") (pinfunction "VDD_32") (pintype "unspecified"))
      (node (ref "U1") (pin "48") (pinfunction "VDD_USB_48") (pintype "unspecified"))
      (node (ref "U1") (pin "64") (pinfunction "VDD_64") (pintype "unspecified"))
      (node (ref "U14") (pin "8") (pinfunction "VCC_8") (pintype "unspecified"))
      (node (ref "U2") (pin "10") (pinfunction "MR#_10") (pintype "unspecified"))
      (node (ref "U2") (pin "16") (pinfunction "VCC_16") (pintype "unspecified"))
      (node (ref "U8") (pin "3") (pinfunction "VDD_3") (pintype "unspecified"))
      (node (ref "U9") (pin "2") (pinfunction "VOUT_2") (pintype "unspecified"))
    )
    (net (code "2") (name "+5V") (class "Default")
      (node (ref "C4") (pin "2") (pinfunction "2_2") (pintype "unspecified"))
      (node (ref "C5") (pin "1") (pinfunction "1_1") (pintype "unspecified"))
      (node (ref "H11") (pin "1") (pinfunction "1_1") (pintype "unspecified"))
      (node (ref "H2") (pin "6") (pinfunction "6_6") (pintype "input"))
      (node (ref "H22") (pin "1") (pinfunction "1_1") (pintype "unspecified"))
      (node (ref "H23") (pin "1") (pinfunction "1_1") (pintype "unspecified"))
      (node (ref "H27") (pin "4") (pinfunction "4_4") (pintype "input"))
      (node (ref "H27") (pin "5") (pinfunction "5_5") (pintype "input"))
      (node (ref "H27") (pin "6") (pinfunction "6_6") (pintype "input"))
      (node (ref "R52") (pin "2") (pinfunction "2_2") (pintype "input"))
      (node (ref "U13") (pin "B3") (pinfunction "Vbus_B3") (pintype "unspecified"))
      (node (ref "U4") (pin "A4B9") (pinfunction "VBUS_A4B9") (pintype "unspecified"))
      (node (ref "U4") (pin "B4A9") (pinfunction "VBUS_B4A9") (pintype "unspecified"))
      (node (ref "U9") (pin "3") (pinfunction "VIN_3") (pintype "unspecified"))
    )
    (net (code "3") (name "/D+IN") (class "Default")
      (node (ref "R62") (pin "1") (pinfunction "1_1") (pintype "input"))
      (node (ref "U13") (pin "C1") (pinfunction "D+in_C1") (pintype "unspecified"))
      (node (ref "U4") (pin "A6") (pinfunction "DP1_A6") (pintype "unspecified"))
    )
    (net (code "4") (name "/D-IN") (class "Default")
      (node (ref "R61") (pin "1") (pinfunction "1_1") (pintype "input"))
      (node (ref "U13") (pin "D1") (pinfunction "D-in_D1") (pintype "unspecified"))
      (node (ref "U4") (pin "A7") (pinfunction "DN1_A7") (pintype "unspecified"))
    )
    (net (code "5") (name "/RS_LED") (class "Default")
      (node (ref "LED11") (pin "1") (pinfunction "K_1") (pintype "unspecified"))
      (node (ref "P1") (pin "1") (pinfunction "1_1") (pintype "input"))
      (node (ref "R39") (pin "1") (pinfunction "1_1") (pintype "input"))
      (node (ref "R40") (pin "2") (pinfunction "2_2") (pintype "input"))
      (node (ref "U14") (pin "6") (pinfunction "A_6") (pintype "unspecified"))
    )
    (net (code "6") (name "/SEGA") (class "Default")
      (node (ref "LED1") (pin "7") (pinfunction "A_7") (pintype "input"))
      (node (ref "R8") (pin "2") (pinfunction "2_2") (pintype "input"))
    )
    (net (code "7") (name "/SEGB") (class "Default")
      (node (ref "LED1") (pin "6") (pinfunction "B_6") (pintype "input"))
      (node (ref "R1") (pin "1") (pinfunction "1_1") (pintype "input"))
    )
    (net (code "8") (name "/SEGC") (class "Default")
      (node (ref "LED1") (pin "4") (pinfunction "C_4") (pintype "input"))
      (node (ref "R2") (pin "1") (pinfunction "1_1") (pintype "input"))
    )
    (net (code "9") (name "/SEGD") (class "Default")
      (node (ref "LED1") (pin "2") (pinfunction "D_2") (pintype "input"))
      (node (ref "R3") (pin "1") (pinfunction "1_1") (pintype "input"))
    )
    (net (code "10") (name "/SEGDP") (class "Default")
      (node (ref "LED1") (pin "5") (pinfunction "DP_5") (pintype "input"))
      (node (ref "R7") (pin "1") (pinfunction "1_1") (pintype "input"))
    )
    (net (code "11") (name "/SEGE") (class "Default")
      (node (ref "LED1") (pin "1") (pinfunction "E_1") (pintype "input"))
      (node (ref "R4") (pin "1") (pinfunction "1_1") (pintype "input"))
    )
    (net (code "12") (name "/SEGF") (class "Default")
      (node (ref "LED1") (pin "9") (pinfunction "F_9") (pintype "input"))
      (node (ref "R5") (pin "1") (pinfunction "1_1") (pintype "input"))
    )
    (net (code "13") (name "/SEGG") (class "Default")
      (node (ref "LED1") (pin "10") (pinfunction "G_10") (pintype "input"))
      (node (ref "R6") (pin "1") (pinfunction "1_1") (pintype "input"))
    )
    (net (code "14") (name "BOOT0") (class "Default")
      (node (ref "R30") (pin "1") (pinfunction "1_1") (pintype "input"))
      (node (ref "R60") (pin "1") (pinfunction "1_1") (pintype "input"))
      (node (ref "U1") (pin "60") (pinfunction "BOOT0_60") (pintype "unspecified"))
    )
    (net (code "15") (name "D+") (class "Default")
      (node (ref "R62") (pin "2") (pinfunction "2_2") (pintype "input"))
      (node (ref "U1") (pin "45") (pinfunction "PA12_45") (pintype "unspecified"))
      (node (ref "U13") (pin "C3") (pinfunction "D+out_C3") (pintype "unspecified"))
    )
    (net (code "16") (name "D-") (class "Default")
      (node (ref "R61") (pin "2") (pinfunction "2_2") (pintype "input"))
      (node (ref "U1") (pin "44") (pinfunction "PA11_44") (pintype "unspecified"))
      (node (ref "U13") (pin "D3") (pinfunction "D-out_D3") (pintype "unspecified"))
    )
    (net (code "17") (name "GND") (class "Default")
      (node (ref "C1") (pin "1") (pinfunction "1_1") (pintype "unspecified"))
      (node (ref "C10") (pin "2") (pinfunction "2_2") (pintype "unspecified"))
      (node (ref "C14") (pin "1") (pinfunction "1_1") (pintype "unspecified"))
      (node (ref "C15") (pin "1") (pinfunction "1_1") (pintype "unspecified"))
      (node (ref "C16") (pin "1") (pinfunction "1_1") (pintype "input"))
      (node (ref "C17") (pin "1") (pinfunction "1_1") (pintype "input"))
      (node (ref "C2") (pin "1") (pinfunction "1_1") (pintype "unspecified"))
      (node (ref "C20") (pin "1") (pinfunction "1_1") (pintype "unspecified"))
      (node (ref "C23") (pin "2") (pinfunction "2_2") (pintype "unspecified"))
      (node (ref "C24") (pin "2") (pinfunction "2_2") (pintype "unspecified"))
      (node (ref "C25") (pin "2") (pinfunction "2_2") (pintype "unspecified"))
      (node (ref "C26") (pin "2") (pinfunction "2_2") (pintype "unspecified"))
      (node (ref "C3") (pin "1") (pinfunction "1_1") (pintype "unspecified"))
      (node (ref "C4") (pin "1") (pinfunction "1_1") (pintype "unspecified"))
      (node (ref "C5") (pin "2") (pinfunction "2_2") (pintype "unspecified"))
      (node (ref "C6") (pin "2") (pinfunction "2_2") (pintype "unspecified"))
      (node (ref "C7") (pin "1") (pinfunction "1_1") (pintype "unspecified"))
      (node (ref "C8") (pin "2") (pinfunction "2_2") (pintype "unspecified"))
      (node (ref "C9") (pin "2") (pinfunction "2_2") (pintype "unspecified"))
      (node (ref "H11") (pin "4") (pinfunction "4_4") (pintype "unspecified"))
      (node (ref "H12") (pin "1") (pinfunction "1_1") (pintype "unspecified"))
      (node (ref "H15") (pin "1") (pinfunction "1_1") (pintype "unspecified"))
      (node (ref "H17") (pin "1") (pinfunction "1_1") (pintype "input"))
      (node (ref "H2") (pin "5") (pinfunction "5_5") (pintype "input"))
      (node (ref "H20") (pin "1") (pinfunction "1_1") (pintype "input"))
      (node (ref "H21") (pin "1") (pinfunction "1_1") (pintype "input"))
      (node (ref "H22") (pin "4") (pinfunction "4_4") (pintype "unspecified"))
      (node (ref "H23") (pin "4") (pinfunction "4_4") (pintype "unspecified"))
      (node (ref "H28") (pin "4") (pinfunction "4_4") (pintype "unspecified"))
      (node (ref "H29") (pin "4") (pinfunction "4_4") (pintype "unspecified"))
      (node (ref "H7") (pin "1") (pinfunction "1_1") (pintype "unspecified"))
      (node (ref "H7") (pin "2") (pinfunction "2_2") (pintype "unspecified"))
      (node (ref "H7") (pin "3") (pinfunction "3_3") (pintype "unspecified"))
      (node (ref "H7") (pin "4") (pinfunction "4_4") (pintype "unspecified"))
      (node (ref "H8") (pin "2") (pinfunction "2_2") (pintype "unspecified"))
      (node (ref "H9") (pin "4") (pinfunction "4_4") (pintype "unspecified"))
      (node (ref "LED10") (pin "1") (pinfunction "K_1") (pintype "input"))
      (node (ref "LED12") (pin "1") (pinfunction "K_1") (pintype "unspecified"))
      (node (ref "LED13") (pin "2") (pinfunction "2_2") (pintype "input"))
      (node (ref "LED14") (pin "2") (pinfunction "2_2") (pintype "input"))
      (node (ref "LED15") (pin "2") (pinfunction "C_2") (pintype "unspecified"))
      (node (ref "LED16") (pin "2") (pinfunction "K_2") (pintype "unspecified"))
      (node (ref "LED9") (pin "1") (pinfunction "K_1") (pintype "input"))
      (node (ref "R19") (pin "1") (pinfunction "1_1") (pintype "input"))
      (node (ref "R20") (pin "1") (pinfunction "1_1") (pintype "input"))
      (node (ref "R21") (pin "1") (pinfunction "1_1") (pintype "input"))
      (node (ref "R29") (pin "1") (pinfunction "1_1") (pintype "input"))
      (node (ref "R38") (pin "2") (pinfunction "2_2") (pintype "input"))
      (node (ref "R65") (pin "1") (pinfunction "1_1") (pintype "input"))
      (node (ref "R66") (pin "1") (pinfunction "1_1") (pintype "input"))
      (node (ref "R67") (pin "1") (pinfunction "1_1") (pintype "input"))
      (node (ref "SW1") (pin "1") (pinfunction "1_1") (pintype "unspecified"))
      (node (ref "SW11") (pin "1") (pinfunction "1_1") (pintype "unspecified"))
      (node (ref "SW11") (pin "2") (pinfunction "2_2") (pintype "unspecified"))
      (node (ref "SW2") (pin "1") (pinfunction "1_1") (pintype "unspecified"))
      (node (ref "SW3") (pin "1") (pinfunction "1_1") (pintype "unspecified"))
      (node (ref "SW4") (pin "1") (pinfunction "1_1") (pintype "unspecified"))
      (node (ref "U1") (pin "12") (pinfunction "VSSA_12") (pintype "unspecified"))
      (node (ref "U1") (pin "18") (pinfunction "VSS_18") (pintype "unspecified"))
      (node (ref "U1") (pin "31") (pinfunction "VSS_31") (pintype "unspecified"))
      (node (ref "U1") (pin "47") (pinfunction "VSS_47") (pintype "unspecified"))
      (node (ref "U1") (pin "63") (pinfunction "VSS_63") (pintype "unspecified"))
      (node (ref "U13") (pin "D2") (pinfunction "GND_D2") (pintype "unspecified"))
      (node (ref "U14") (pin "5") (pinfunction "VO1_5") (pintype "unspecified"))
      (node (ref "U2") (pin "8") (pinfunction "GND_8") (pintype "unspecified"))
      (node (ref "U4") (pin "A1B12") (pinfunction "GND_A1B12") (pintype "unspecified"))
      (node (ref "U4") (pin "B1A12") (pinfunction "GND_B1A12") (pintype "unspecified"))
      (node (ref "U8") (pin "1") (pinfunction "GND_1") (pintype "unspecified"))
      (node (ref "U9") (pin "1") (pinfunction "GND_1") (pintype "unspecified"))
    )
    (net (code "18") (name "NRST") (class "Default")
      (node (ref "H2") (pin "4") (pinfunction "4_4") (pintype "input"))
      (node (ref "U1") (pin "7") (pinfunction "NRST_7") (pintype "unspecified"))
    )
    (net (code "19") (name "Net-(C21-Pad2)") (class "Default")
      (node (ref "C21") (pin "2") (pinfunction "2_2") (pintype "unspecified"))
      (node (ref "C22") (pin "2") (pinfunction "2_2") (pintype "unspecified"))
    )
    (net (code "20") (name "Net-(C23-Pad1)") (class "Default")
      (node (ref "C23") (pin "1") (pinfunction "1_1") (pintype "unspecified"))
      (node (ref "SW1") (pin "3") (pinfunction "3_3") (pintype "unspecified"))
    )
    (net (code "21") (name "Net-(C24-Pad1)") (class "Default")
      (node (ref "C24") (pin "1") (pinfunction "1_1") (pintype "unspecified"))
      (node (ref "SW2") (pin "3") (pinfunction "3_3") (pintype "unspecified"))
    )
    (net (code "22") (name "Net-(C25-Pad1)") (class "Default")
      (node (ref "C25") (pin "1") (pinfunction "1_1") (pintype "unspecified"))
      (node (ref "SW3") (pin "3") (pinfunction "3_3") (pintype "unspecified"))
    )
    (net (code "23") (name "Net-(C26-Pad1)") (class "Default")
      (node (ref "C26") (pin "1") (pinfunction "1_1") (pintype "unspecified"))
      (node (ref "SW4") (pin "3") (pinfunction "3_3") (pintype "unspecified"))
    )
    (net (code "24") (name "Net-(H8-Pad1)") (class "Default")
      (node (ref "H8") (pin "1") (pinfunction "1_1") (pintype "unspecified"))
      (node (ref "R60") (pin "2") (pinfunction "2_2") (pintype "input"))
    )
    (net (code "25") (name "Net-(LED8-+)") (class "Default")
      (node (ref "LED8") (pin "1") (pinfunction "+_1") (pintype "unspecified"))
      (node (ref "R59") (pin "1") (pinfunction "1_1") (pintype "input"))
    )
    (net (code "26") (name "Net-(LED9-A)") (class "Default")
      (node (ref "LED9") (pin "2") (pinfunction "A_2") (pintype "input"))
      (node (ref "R51") (pin "1") (pinfunction "1_1") (pintype "input"))
    )
    (net (code "27") (name "Net-(LED10-A)") (class "Default")
      (node (ref "LED10") (pin "2") (pinfunction "A_2") (pintype "input"))
      (node (ref "R52") (pin "1") (pinfunction "1_1") (pintype "input"))
    )
    (net (code "28") (name "Net-(LED11-A)") (class "Default")
      (node (ref "LED11") (pin "2") (pinfunction "A_2") (pintype "unspecified"))
      (node (ref "R57") (pin "1") (pinfunction "1_1") (pintype "input"))
    )
    (net (code "29") (name "Net-(LED12-A)") (class "Default")
      (node (ref "LED12") (pin "2") (pinfunction "A_2") (pintype "unspecified"))
      (node (ref "R10") (pin "1") (pinfunction "1_1") (pintype "input"))
    )
    (net (code "30") (name "Net-(LED13-Pad1)") (class "Default")
      (node (ref "LED13") (pin "1") (pinfunction "1_1") (pintype "input"))
      (node (ref "R12") (pin "1") (pinfunction "1_1") (pintype "input"))
    )
    (net (code "31") (name "Net-(LED14-Pad1)") (class "Default")
      (node (ref "LED14") (pin "1") (pinfunction "1_1") (pintype "input"))
      (node (ref "R13") (pin "1") (pinfunction "1_1") (pintype "input"))
    )
    (net (code "32") (name "Net-(LED15-A)") (class "Default")
      (node (ref "LED15") (pin "1") (pinfunction "A_1") (pintype "unspecified"))
      (node (ref "R11") (pin "1") (pinfunction "1_1") (pintype "input"))
    )
    (net (code "33") (name "Net-(LED16-A)") (class "Default")
      (node (ref "LED16") (pin "1") (pinfunction "A_1") (pintype "unspecified"))
      (node (ref "R9") (pin "1") (pinfunction "1_1") (pintype "input"))
    )
    (net (code "34") (name "Net-(LED17-+)") (class "Default")
      (node (ref "LED17") (pin "1") (pinfunction "+_1") (pintype "unspecified"))
      (node (ref "R58") (pin "1") (pinfunction "1_1") (pintype "input"))
    )
    (net (code "35") (name "Net-(U1-PH0-OSC_IN)") (class "Default")
      (node (ref "C16") (pin "2") (pinfunction "2_2") (pintype "input"))
      (node (ref "U1") (pin "5") (pinfunction "PH0-OSC_IN_5") (pintype "unspecified"))
      (node (ref "X1") (pin "3") (pinfunction "OSC2_3") (pintype "input"))
    )
    (net (code "36") (name "Net-(U1-PH1-OSC_OUT)") (class "Default")
      (node (ref "C17") (pin "2") (pinfunction "2_2") (pintype "input"))
      (node (ref "U1") (pin "6") (pinfunction "PH1-OSC_OUT_6") (pintype "unspecified"))
      (node (ref "X1") (pin "1") (pinfunction "OSC1_1") (pintype "input"))
    )
    (net (code "37") (name "Net-(U2-Q0)") (class "Default")
      (node (ref "R8") (pin "1") (pinfunction "1_1") (pintype "input"))
      (node (ref "U2") (pin "15") (pinfunction "Q0_15") (pintype "unspecified"))
    )
    (net (code "38") (name "Net-(U2-Q1)") (class "Default")
      (node (ref "R1") (pin "2") (pinfunction "2_2") (pintype "input"))
      (node (ref "U2") (pin "1") (pinfunction "Q1_1") (pintype "unspecified"))
    )
    (net (code "39") (name "Net-(U2-Q2)") (class "Default")
      (node (ref "R2") (pin "2") (pinfunction "2_2") (pintype "input"))
      (node (ref "U2") (pin "2") (pinfunction "Q2_2") (pintype "unspecified"))
    )
    (net (code "40") (name "Net-(U2-Q3)") (class "Default")
      (node (ref "R3") (pin "2") (pinfunction "2_2") (pintype "input"))
      (node (ref "U2") (pin "3") (pinfunction "Q3_3") (pintype "unspecified"))
    )
    (net (code "41") (name "Net-(U2-Q4)") (class "Default")
      (node (ref "R4") (pin "2") (pinfunction "2_2") (pintype "input"))
      (node (ref "U2") (pin "4") (pinfunction "Q4_4") (pintype "unspecified"))
    )
    (net (code "42") (name "Net-(U2-Q5)") (class "Default")
      (node (ref "R5") (pin "2") (pinfunction "2_2") (pintype "input"))
      (node (ref "U2") (pin "5") (pinfunction "Q5_5") (pintype "unspecified"))
    )
    (net (code "43") (name "Net-(U2-Q6)") (class "Default")
      (node (ref "R6") (pin "2") (pinfunction "2_2") (pintype "input"))
      (node (ref "U2") (pin "6") (pinfunction "Q6_6") (pintype "unspecified"))
    )
    (net (code "44") (name "Net-(U2-Q7)") (class "Default")
      (node (ref "R7") (pin "2") (pinfunction "2_2") (pintype "input"))
      (node (ref "U2") (pin "7") (pinfunction "Q7_7") (pintype "unspecified"))
    )
    (net (code "45") (name "Net-(U14-B)") (class "Default")
      (node (ref "P1") (pin "2") (pinfunction "2_2") (pintype "input"))
      (node (ref "R38") (pin "1") (pinfunction "1_1") (pintype "input"))
      (node (ref "R39") (pin "2") (pinfunction "2_2") (pintype "input"))
      (node (ref "U14") (pin "7") (pinfunction "B_7") (pintype "unspecified"))
    )
    (net (code "46") (name "PA0") (class "Default")
      (node (ref "C1") (pin "2") (pinfunction "2_2") (pintype "unspecified"))
      (node (ref "R19") (pin "2") (pinfunction "2_2") (pintype "input"))
      (node (ref "R65") (pin "2") (pinfunction "2_2") (pintype "input"))
      (node (ref "U1") (pin "14") (pinfunction "PA0_14") (pintype "unspecified"))
    )
    (net (code "47") (name "PA1") (class "Default")
      (node (ref "C2") (pin "2") (pinfunction "2_2") (pintype "unspecified"))
      (node (ref "R20") (pin "2") (pinfunction "2_2") (pintype "input"))
      (node (ref "R66") (pin "2") (pinfunction "2_2") (pintype "input"))
      (node (ref "U1") (pin "15") (pinfunction "PA1_15") (pintype "unspecified"))
    )
    (net (code "48") (name "PA2") (class "Default")
      (node (ref "C3") (pin "2") (pinfunction "2_2") (pintype "unspecified"))
      (node (ref "R21") (pin "2") (pinfunction "2_2") (pintype "input"))
      (node (ref "R67") (pin "2") (pinfunction "2_2") (pintype "input"))
      (node (ref "U1") (pin "16") (pinfunction "PA2_16") (pintype "unspecified"))
    )
    (net (code "49") (name "PA3") (class "Default")
      (node (ref "R27") (pin "1") (pinfunction "1_1") (pintype "input"))
      (node (ref "U1") (pin "17") (pinfunction "PA3_17") (pintype "unspecified"))
      (node (ref "U8") (pin "2") (pinfunction "DQ_2") (pintype "unspecified"))
    )
    (net (code "50") (name "PA4") (class "Default")
      (node (ref "R28") (pin "2") (pinfunction "2_2") (pintype "input"))
      (node (ref "R29") (pin "2") (pinfunction "2_2") (pintype "input"))
      (node (ref "U1") (pin "20") (pinfunction "PA4_20") (pintype "unspecified"))
    )
    (net (code "51") (name "PA5") (class "Default")
      (node (ref "H12") (pin "2") (pinfunction "2_2") (pintype "unspecified"))
      (node (ref "U1") (pin "21") (pinfunction "PA5_21") (pintype "unspecified"))
    )
    (net (code "52") (name "PA6") (class "Default")
      (node (ref "H13") (pin "1") (pinfunction "1_1") (pintype "unspecified"))
      (node (ref "U1") (pin "22") (pinfunction "PA6_22") (pintype "unspecified"))
    )
    (net (code "53") (name "PA7") (class "Default")
      (node (ref "H13") (pin "2") (pinfunction "2_2") (pintype "unspecified"))
      (node (ref "U1") (pin "23") (pinfunction "PA7_23") (pintype "unspecified"))
    )
    (net (code "54") (name "PA8") (class "Default")
      (node (ref "R9") (pin "2") (pinfunction "2_2") (pintype "input"))
      (node (ref "U1") (pin "41") (pinfunction "PA8_41") (pintype "unspecified"))
    )
    (net (code "55") (name "PA9") (class "Default")
      (node (ref "H28") (pin "3") (pinfunction "3_3") (pintype "unspecified"))
      (node (ref "H29") (pin "3") (pinfunction "3_3") (pintype "unspecified"))
      (node (ref "H9") (pin "3") (pinfunction "3_3") (pintype "unspecified"))
      (node (ref "LED8") (pin "2") (pinfunction "-_2") (pintype "unspecified"))
      (node (ref "U1") (pin "42") (pinfunction "PA9_42") (pintype "unspecified"))
    )
    (net (code "56") (name "PA10") (class "Default")
      (node (ref "H28") (pin "2") (pinfunction "2_2") (pintype "unspecified"))
      (node (ref "H29") (pin "2") (pinfunction "2_2") (pintype "unspecified"))
      (node (ref "H9") (pin "2") (pinfunction "2_2") (pintype "unspecified"))
      (node (ref "LED17") (pin "2") (pinfunction "-_2") (pintype "unspecified"))
      (node (ref "U1") (pin "43") (pinfunction "PA10_43") (pintype "unspecified"))
    )
    (net (code "57") (name "PA13") (class "Default")
      (node (ref "H2") (pin "3") (pinfunction "3_3") (pintype "input"))
      (node (ref "U1") (pin "46") (pinfunction "PA13_46") (pintype "unspecified"))
    )
    (net (code "58") (name "PA14") (class "Default")
      (node (ref "H2") (pin "2") (pinfunction "2_2") (pintype "input"))
      (node (ref "U1") (pin "49") (pinfunction "PA14_49") (pintype "unspecified"))
    )
    (net (code "59") (name "PA15") (class "Default")
      (node (ref "H17") (pin "2") (pinfunction "2_2") (pintype "input"))
      (node (ref "H20") (pin "2") (pinfunction "2_2") (pintype "input"))
      (node (ref "H21") (pin "2") (pinfunction "2_2") (pintype "input"))
      (node (ref "U1") (pin "50") (pinfunction "PA15_50") (pintype "unspecified"))
    )
    (net (code "60") (name "PB0") (class "Default")
      (node (ref "C14") (pin "2") (pinfunction "2_2") (pintype "unspecified"))
      (node (ref "R34") (pin "2") (pinfunction "2_2") (pintype "input"))
      (node (ref "SW11") (pin "3") (pinfunction "3_3") (pintype "unspecified"))
      (node (ref "U1") (pin "26") (pinfunction "PB0_26") (pintype "unspecified"))
    )
    (net (code "61") (name "PB1") (class "Default")
      (node (ref "R22") (pin "1") (pinfunction "1_1") (pintype "input"))
      (node (ref "SW1") (pin "4") (pinfunction "4_4") (pintype "unspecified"))
      (node (ref "U1") (pin "27") (pinfunction "PB1_27") (pintype "unspecified"))
    )
    (net (code "62") (name "PB2") (class "Default")
      (node (ref "R23") (pin "2") (pinfunction "2_2") (pintype "input"))
      (node (ref "SW2") (pin "4") (pinfunction "4_4") (pintype "unspecified"))
      (node (ref "U1") (pin "28") (pinfunction "PB2_28") (pintype "unspecified"))
    )
    (net (code "63") (name "PB3") (class "Default")
      (node (ref "H17") (pin "3") (pinfunction "3_3") (pintype "input"))
      (node (ref "H20") (pin "3") (pinfunction "3_3") (pintype "input"))
      (node (ref "H21") (pin "3") (pinfunction "3_3") (pintype "input"))
      (node (ref "U1") (pin "55") (pinfunction "PB3_55") (pintype "unspecified"))
    )
    (net (code "64") (name "PB4") (class "Default")
      (node (ref "H17") (pin "4") (pinfunction "4_4") (pintype "input"))
      (node (ref "H20") (pin "4") (pinfunction "4_4") (pintype "input"))
      (node (ref "H21") (pin "4") (pinfunction "4_4") (pintype "input"))
      (node (ref "U1") (pin "56") (pinfunction "PB4_56") (pintype "unspecified"))
    )
    (net (code "65") (name "PB5") (class "Default")
      (node (ref "H17") (pin "5") (pinfunction "5_5") (pintype "input"))
      (node (ref "H20") (pin "5") (pinfunction "5_5") (pintype "input"))
      (node (ref "H21") (pin "5") (pinfunction "5_5") (pintype "input"))
      (node (ref "U1") (pin "57") (pinfunction "PB5_57") (pintype "unspecified"))
    )
    (net (code "66") (name "PB7") (class "Default")
      (node (ref "H15") (pin "2") (pinfunction "2_2") (pintype "unspecified"))
      (node (ref "U1") (pin "59") (pinfunction "PB7_59") (pintype "unspecified"))
    )
    (net (code "67") (name "PB8") (class "Default")
      (node (ref "H11") (pin "3") (pinfunction "3_3") (pintype "unspecified"))
      (node (ref "H22") (pin "3") (pinfunction "3_3") (pintype "unspecified"))
      (node (ref "H23") (pin "3") (pinfunction "3_3") (pintype "unspecified"))
      (node (ref "U1") (pin "61") (pinfunction "PB8_61") (pintype "unspecified"))
    )
    (net (code "68") (name "PB9") (class "Default")
      (node (ref "H11") (pin "2") (pinfunction "2_2") (pintype "unspecified"))
      (node (ref "H22") (pin "2") (pinfunction "2_2") (pintype "unspecified"))
      (node (ref "H23") (pin "2") (pinfunction "2_2") (pintype "unspecified"))
      (node (ref "U1") (pin "62") (pinfunction "PB9_62") (pintype "unspecified"))
    )
    (net (code "69") (name "PB10") (class "Default")
      (node (ref "R24") (pin "2") (pinfunction "2_2") (pintype "input"))
      (node (ref "SW3") (pin "4") (pinfunction "4_4") (pintype "unspecified"))
      (node (ref "U1") (pin "29") (pinfunction "PB10_29") (pintype "unspecified"))
    )
    (net (code "70") (name "PB11") (class "Default")
      (node (ref "R25") (pin "1") (pinfunction "1_1") (pintype "input"))
      (node (ref "SW4") (pin "4") (pinfunction "4_4") (pintype "unspecified"))
      (node (ref "U1") (pin "30") (pinfunction "PB11_30") (pintype "unspecified"))
    )
    (net (code "71") (name "PB12") (class "Default")
      (node (ref "U1") (pin "36") (pinfunction "PB15_36") (pintype "unspecified"))
      (node (ref "U2") (pin "13") (pinfunction "OE#_13") (pintype "unspecified"))
    )
    (net (code "72") (name "PB13") (class "Default")
      (node (ref "U1") (pin "35") (pinfunction "PB14_35") (pintype "unspecified"))
      (node (ref "U2") (pin "11") (pinfunction "SHCP_11") (pintype "unspecified"))
    )
    (net (code "73") (name "PB14") (class "Default")
      (node (ref "U1") (pin "34") (pinfunction "PB13_34") (pintype "unspecified"))
      (node (ref "U2") (pin "12") (pinfunction "STCP_12") (pintype "unspecified"))
    )
    (net (code "74") (name "PB15") (class "Default")
      (node (ref "U1") (pin "33") (pinfunction "PB12_33") (pintype "unspecified"))
      (node (ref "U2") (pin "14") (pinfunction "DS_14") (pintype "unspecified"))
    )
    (net (code "75") (name "PC0") (class "Default")
      (node (ref "H3") (pin "4") (pinfunction "4_4") (pintype "unspecified"))
      (node (ref "U1") (pin "8") (pinfunction "PC0_8") (pintype "unspecified"))
    )
    (net (code "76") (name "PC1") (class "Default")
      (node (ref "H3") (pin "3") (pinfunction "3_3") (pintype "unspecified"))
      (node (ref "U1") (pin "9") (pinfunction "PC1_9") (pintype "unspecified"))
    )
    (net (code "77") (name "PC2") (class "Default")
      (node (ref "H3") (pin "2") (pinfunction "2_2") (pintype "unspecified"))
      (node (ref "U1") (pin "10") (pinfunction "PC2_10") (pintype "unspecified"))
    )
    (net (code "78") (name "PC3") (class "Default")
      (node (ref "H3") (pin "1") (pinfunction "1_1") (pintype "unspecified"))
      (node (ref "U1") (pin "11") (pinfunction "PC3_11") (pintype "unspecified"))
    )
    (net (code "79") (name "PC5") (class "Default")
      (node (ref "C15") (pin "2") (pinfunction "2_2") (pintype "unspecified"))
      (node (ref "R33") (pin "2") (pinfunction "2_2") (pintype "input"))
      (node (ref "SW11") (pin "4") (pinfunction "4_4") (pintype "unspecified"))
      (node (ref "U1") (pin "25") (pinfunction "PC5_25") (pintype "unspecified"))
    )
    (net (code "80") (name "PC6") (class "Default")
      (node (ref "R13") (pin "2") (pinfunction "2_2") (pintype "input"))
      (node (ref "U1") (pin "37") (pinfunction "PC6_37") (pintype "unspecified"))
    )
    (net (code "81") (name "PC7") (class "Default")
      (node (ref "R12") (pin "2") (pinfunction "2_2") (pintype "input"))
      (node (ref "U1") (pin "38") (pinfunction "PC7_38") (pintype "unspecified"))
    )
    (net (code "82") (name "PC8") (class "Default")
      (node (ref "R11") (pin "2") (pinfunction "2_2") (pintype "input"))
      (node (ref "U1") (pin "39") (pinfunction "PC8_39") (pintype "unspecified"))
    )
    (net (code "83") (name "PC9") (class "Default")
      (node (ref "R10") (pin "2") (pinfunction "2_2") (pintype "input"))
      (node (ref "U1") (pin "40") (pinfunction "PC9_40") (pintype "unspecified"))
    )
    (net (code "84") (name "PC10") (class "Default")
      (node (ref "R45") (pin "1") (pinfunction "1_1") (pintype "input"))
      (node (ref "U1") (pin "51") (pinfunction "PC10_51") (pintype "unspecified"))
      (node (ref "U14") (pin "4") (pinfunction "DI_4") (pintype "unspecified"))
    )
    (net (code "85") (name "PC11") (class "Default")
      (node (ref "R44") (pin "1") (pinfunction "1_1") (pintype "input"))
      (node (ref "U1") (pin "52") (pinfunction "PC11_52") (pintype "unspecified"))
      (node (ref "U14") (pin "3") (pinfunction "DE_3") (pintype "unspecified"))
    )
    (net (code "86") (name "PC12") (class "Default")
      (node (ref "R43") (pin "1") (pinfunction "1_1") (pintype "input"))
      (node (ref "U1") (pin "53") (pinfunction "PC12_53") (pintype "unspecified"))
      (node (ref "U14") (pin "2") (pinfunction "RE#_2") (pintype "unspecified"))
    )
    (net (code "87") (name "PC15") (class "Default")
      (node (ref "H3") (pin "5") (pinfunction "5_5") (pintype "unspecified"))
      (node (ref "U1") (pin "4") (pinfunction "PC15-OSC32_OUT_4") (pintype "unspecified"))
    )
    (net (code "88") (name "PD2") (class "Default")
      (node (ref "R42") (pin "1") (pinfunction "1_1") (pintype "input"))
      (node (ref "U1") (pin "54") (pinfunction "PD2_54") (pintype "unspecified"))
      (node (ref "U14") (pin "1") (pinfunction "R0_1") (pintype "unspecified"))
    )
    (net (code "89") (name "unconnected-(H2-Pad1)") (class "Default")
      (node (ref "H2") (pin "1") (pinfunction "1_1") (pintype "input+no_connect"))
    )
    (net (code "90") (name "unconnected-(R65-Pad4)") (class "Default")
      (node (ref "R65") (pin "4") (pinfunction "4_4") (pintype "input+no_connect"))
    )
    (net (code "91") (name "unconnected-(R65-Pad5)") (class "Default")
      (node (ref "R65") (pin "5") (pinfunction "5_5") (pintype "input+no_connect"))
    )
    (net (code "92") (name "unconnected-(R66-Pad4)") (class "Default")
      (node (ref "R66") (pin "4") (pinfunction "4_4") (pintype "input+no_connect"))
    )
    (net (code "93") (name "unconnected-(R66-Pad5)") (class "Default")
      (node (ref "R66") (pin "5") (pinfunction "5_5") (pintype "input+no_connect"))
    )
    (net (code "94") (name "unconnected-(R67-Pad4)") (class "Default")
      (node (ref "R67") (pin "4") (pinfunction "4_4") (pintype "input+no_connect"))
    )
    (net (code "95") (name "unconnected-(R67-Pad5)") (class "Default")
      (node (ref "R67") (pin "5") (pinfunction "5_5") (pintype "input+no_connect"))
    )
    (net (code "96") (name "unconnected-(SW1-Pad2)") (class "Default")
      (node (ref "SW1") (pin "2") (pinfunction "2_2") (pintype "unspecified+no_connect"))
    )
    (net (code "97") (name "unconnected-(SW2-Pad2)") (class "Default")
      (node (ref "SW2") (pin "2") (pinfunction "2_2") (pintype "unspecified+no_connect"))
    )
    (net (code "98") (name "unconnected-(SW3-Pad2)") (class "Default")
      (node (ref "SW3") (pin "2") (pinfunction "2_2") (pintype "unspecified+no_connect"))
    )
    (net (code "99") (name "unconnected-(SW4-Pad2)") (class "Default")
      (node (ref "SW4") (pin "2") (pinfunction "2_2") (pintype "unspecified+no_connect"))
    )
    (net (code "100") (name "unconnected-(U1-PB6-Pad58)") (class "Default")
      (node (ref "U1") (pin "58") (pinfunction "PB6_58") (pintype "unspecified+no_connect"))
    )
    (net (code "101") (name "unconnected-(U1-PC4-Pad24)") (class "Default")
      (node (ref "U1") (pin "24") (pinfunction "PC4_24") (pintype "unspecified+no_connect"))
    )
    (net (code "102") (name "unconnected-(U1-PC13-Pad2)") (class "Default")
      (node (ref "U1") (pin "2") (pinfunction "PC13_2") (pintype "unspecified+no_connect"))
    )
    (net (code "103") (name "unconnected-(U1-PC14-OSC32_IN-Pad3)") (class "Default")
      (node (ref "U1") (pin "3") (pinfunction "PC14-OSC32_IN_3") (pintype "unspecified+no_connect"))
    )
    (net (code "104") (name "unconnected-(U2-Q7S-Pad9)") (class "Default")
      (node (ref "U2") (pin "9") (pinfunction "Q7S_9") (pintype "unspecified+no_connect"))
    )
    (net (code "105") (name "unconnected-(U4-CC1-PadA5)") (class "Default")
      (node (ref "U4") (pin "A5") (pinfunction "CC1_A5") (pintype "unspecified+no_connect"))
    )
    (net (code "106") (name "unconnected-(U4-CC2-PadB5)") (class "Default")
      (node (ref "U4") (pin "B5") (pinfunction "CC2_B5") (pintype "unspecified+no_connect"))
    )
    (net (code "107") (name "unconnected-(U4-DN2-PadB7)") (class "Default")
      (node (ref "U4") (pin "B7") (pinfunction "DN2_B7") (pintype "unspecified+no_connect"))
    )
    (net (code "108") (name "unconnected-(U4-DP2-PadB6)") (class "Default")
      (node (ref "U4") (pin "B6") (pinfunction "DP2_B6") (pintype "unspecified+no_connect"))
    )
    (net (code "109") (name "unconnected-(U4-Pad1)") (class "Default")
      (node (ref "U4") (pin "1") (pinfunction "1_1") (pintype "unspecified+no_connect"))
    )
    (net (code "110") (name "unconnected-(U4-Pad2)") (class "Default")
      (node (ref "U4") (pin "2") (pinfunction "2_2") (pintype "unspecified+no_connect"))
    )
    (net (code "111") (name "unconnected-(U4-Pad3)") (class "Default")
      (node (ref "U4") (pin "3") (pinfunction "3_3") (pintype "unspecified+no_connect"))
    )
    (net (code "112") (name "unconnected-(U4-Pad4)") (class "Default")
      (node (ref "U4") (pin "4") (pinfunction "4_4") (pintype "unspecified+no_connect"))
    )
    (net (code "113") (name "unconnected-(U4-SBU1-PadA8)") (class "Default")
      (node (ref "U4") (pin "A8") (pinfunction "SBU1_A8") (pintype "unspecified+no_connect"))
    )
    (net (code "114") (name "unconnected-(U4-SBU2-PadB8)") (class "Default")
      (node (ref "U4") (pin "B8") (pinfunction "SBU2_B8") (pintype "unspecified+no_connect"))
    )
    (net (code "115") (name "unconnected-(U13-Dz-PadA2)") (class "Default")
      (node (ref "U13") (pin "A2") (pinfunction "Dz_A2") (pintype "unspecified+no_connect"))
    )
    (net (code "116") (name "unconnected-(U13-ID-PadA3)") (class "Default")
      (node (ref "U13") (pin "A3") (pinfunction "ID_A3") (pintype "unspecified+no_connect"))
    )
    (net (code "117") (name "unconnected-(U13-Pd1-PadB1)") (class "Default")
      (node (ref "U13") (pin "B1") (pinfunction "Pd1_B1") (pintype "unspecified+no_connect"))
    )
    (net (code "118") (name "unconnected-(U13-Pd2-PadC2)") (class "Default")
      (node (ref "U13") (pin "C2") (pinfunction "Pd2_C2") (pintype "unspecified+no_connect"))
    )
    (net (code "119") (name "unconnected-(U13-Pup-PadB2)") (class "Default")
      (node (ref "U13") (pin "B2") (pinfunction "Pup_B2") (pintype "unspecified+no_connect"))
    )
    (net (code "120") (name "unconnected-(X1-GND-Pad2)") (class "Default")
      (node (ref "X1") (pin "2") (pinfunction "GND_2") (pintype "input+no_connect"))
    )
  )
)
